# Sheet2.net
KiCad netlist of a schematic drawn in Altium Designer
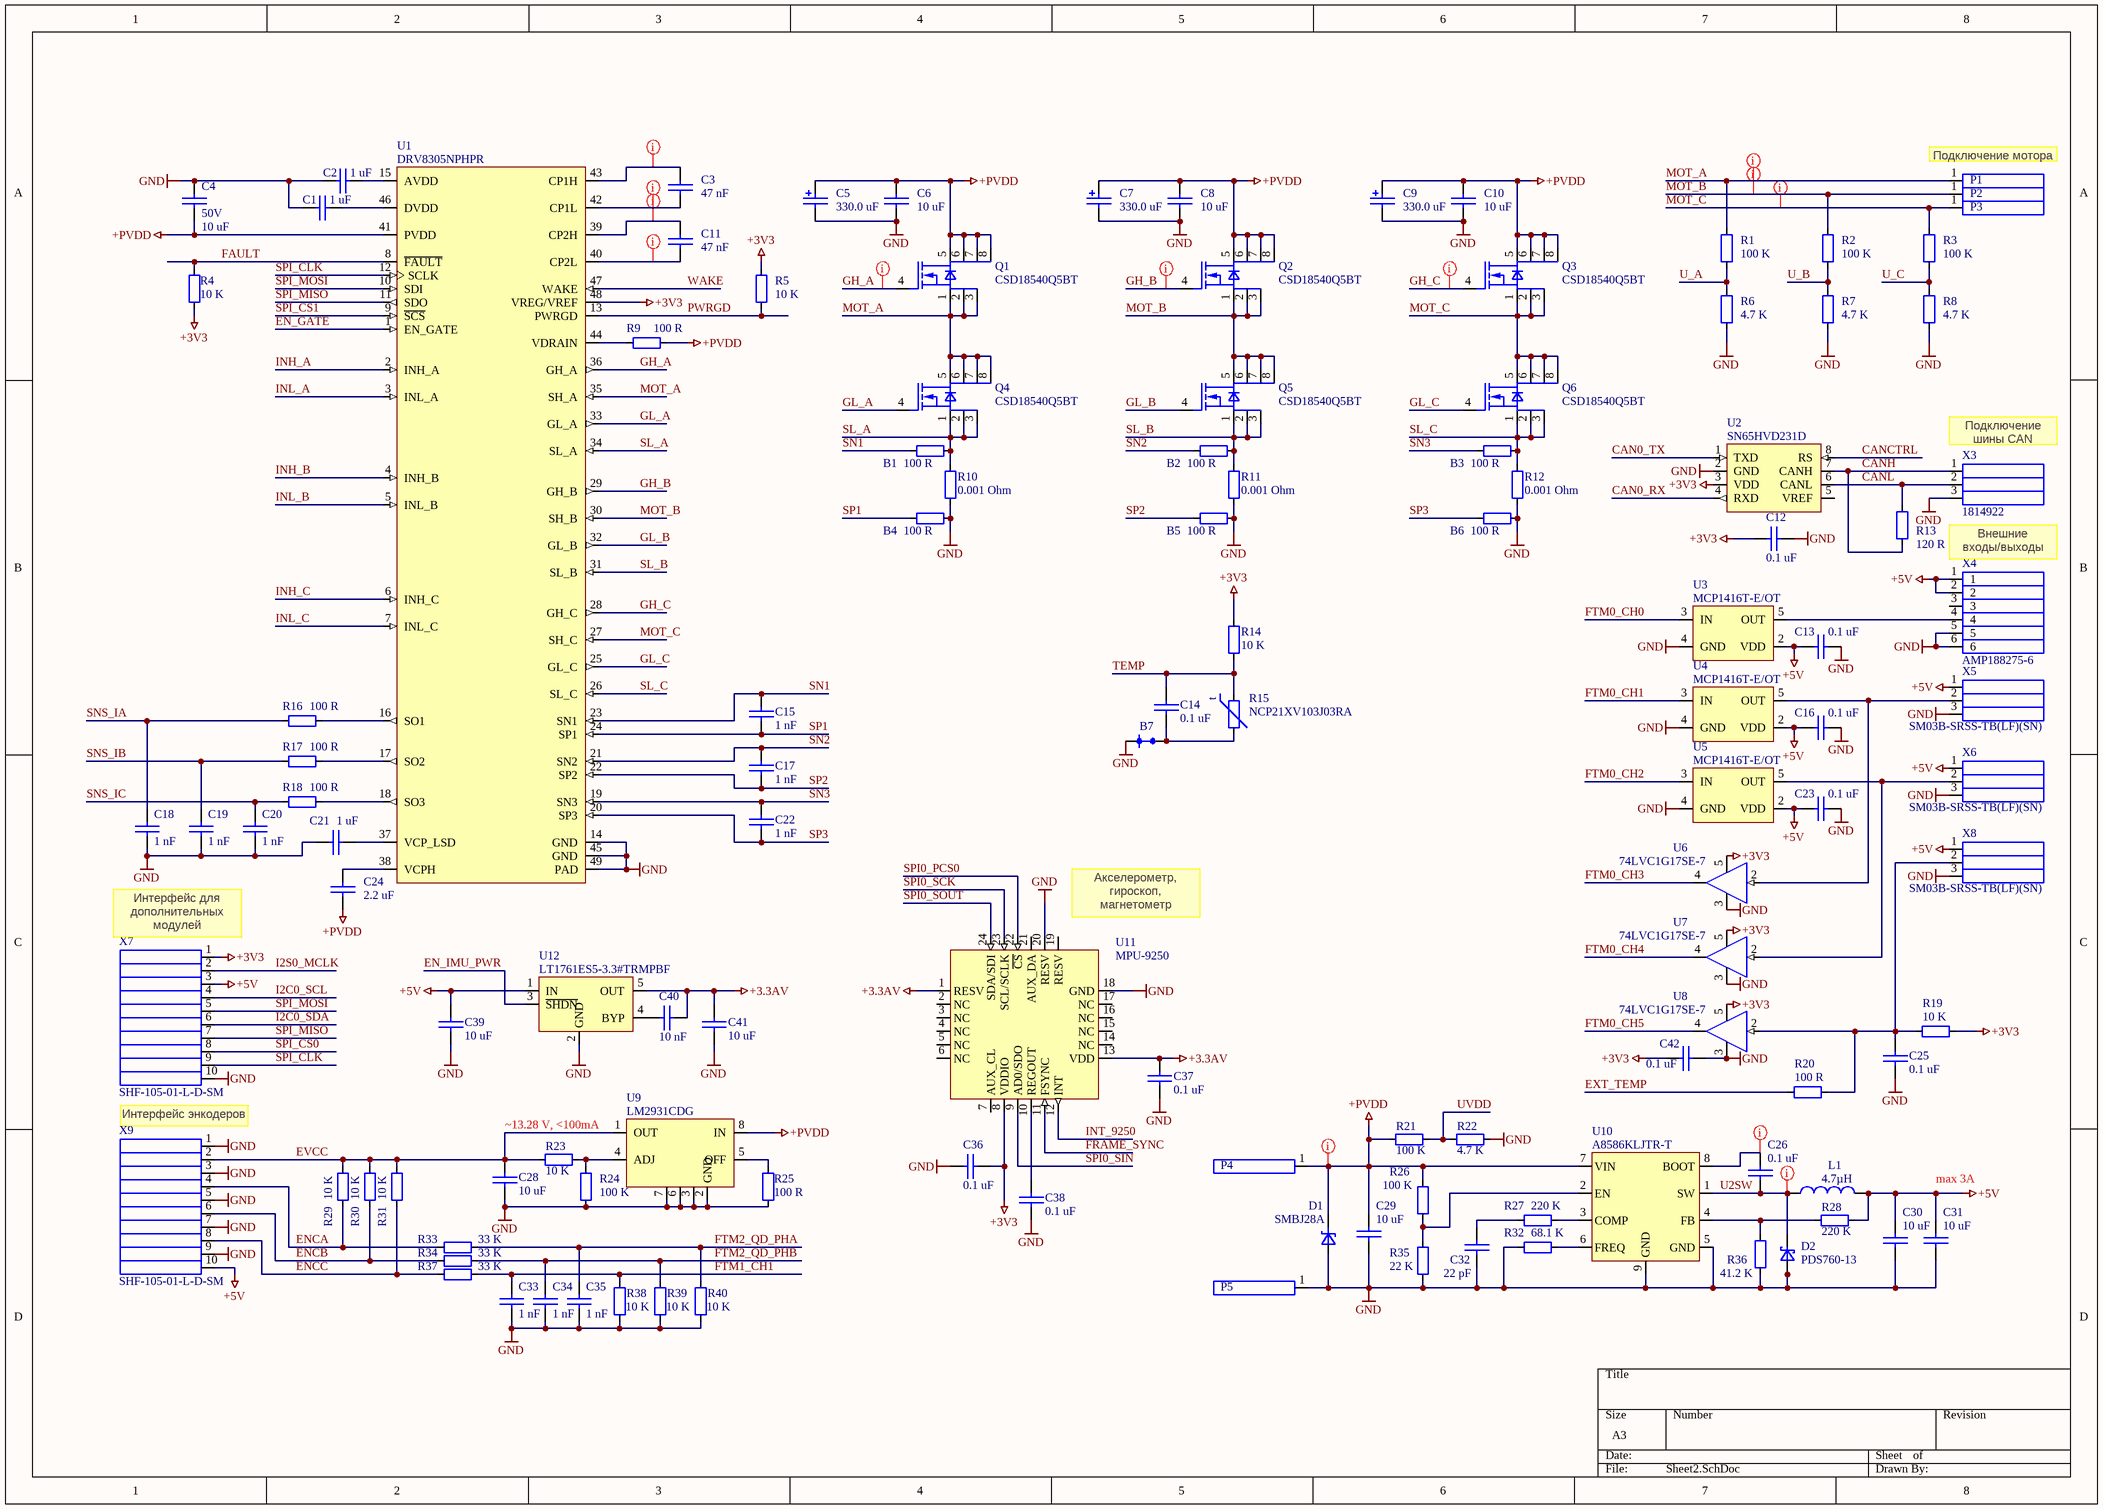
[diagram p0: Sheet2.SchDoc]

(export (version "E")
  (design (tool "Eeschema 10.0.6"))
  (components
    (comp (ref "B1")
      (value "100 R")
      (footprint "0603")
      (description "100 R, 1%, 0603, SMD Resistor, Taped")
      (fields (field (name "MANUFACTURER") "Vishay") (field (name "TOLERANCE") "±1%"))
      (libsource (lib "ea_Resistors") (part "RL0603E100-1"))
    )
    (comp (ref "B2")
      (value "100 R")
      (footprint "0603")
      (description "100 R, 1%, 0603, SMD Resistor, Taped")
      (fields (field (name "MANUFACTURER") "Vishay") (field (name "TOLERANCE") "±1%"))
      (libsource (lib "ea_Resistors") (part "RL0603E100-1"))
    )
    (comp (ref "B3")
      (value "100 R")
      (footprint "0603")
      (description "100 R, 1%, 0603, SMD Resistor, Taped")
      (fields (field (name "MANUFACTURER") "Vishay") (field (name "TOLERANCE") "±1%"))
      (libsource (lib "ea_Resistors") (part "RL0603E100-1"))
    )
    (comp (ref "B4")
      (value "100 R")
      (footprint "0603")
      (description "100 R, 1%, 0603, SMD Resistor, Taped")
      (fields (field (name "MANUFACTURER") "Vishay") (field (name "TOLERANCE") "±1%"))
      (libsource (lib "ea_Resistors") (part "RL0603E100-1"))
    )
    (comp (ref "B5")
      (value "100 R")
      (footprint "0603")
      (description "100 R, 1%, 0603, SMD Resistor, Taped")
      (fields (field (name "MANUFACTURER") "Vishay") (field (name "TOLERANCE") "±1%"))
      (libsource (lib "ea_Resistors") (part "RL0603E100-1"))
    )
    (comp (ref "B6")
      (value "100 R")
      (footprint "0603")
      (description "100 R, 1%, 0603, SMD Resistor, Taped")
      (fields (field (name "MANUFACTURER") "Vishay") (field (name "TOLERANCE") "±1%"))
      (libsource (lib "ea_Resistors") (part "RL0603E100-1"))
    )
    (comp (ref "B7")
      (value "Net tie 0603")
      (footprint "Net tee 0603")
      (libsource (lib "ea_Mechanical") (part "Net tie 0603"))
    )
    (comp (ref "C1")
      (value "1 uF")
      (footprint "1608[0603]")
      (description "1 uF, 16V, 10%, X7R, 0603 SMD MLC Capacitor, -55°C ~ 125°C")
      (fields (field (name "TOLERANCE") "±10%") (field (name "MANUFACTURER") "TDK Corporation"))
      (libsource (lib "ea_Capacitors") (part "C1608X7R1C105K080AC"))
    )
    (comp (ref "C2")
      (value "1 uF")
      (footprint "1608[0603]")
      (description "1 uF, 16V, 10%, X7R, 0603 SMD MLC Capacitor, -55°C ~ 125°C")
      (fields (field (name "TOLERANCE") "±10%") (field (name "MANUFACTURER") "TDK Corporation"))
      (libsource (lib "ea_Capacitors") (part "C1608X7R1C105K080AC"))
    )
    (comp (ref "C3")
      (value "47 nF")
      (footprint "1608[0603]")
      (description "47 nF, 100V, 10%, X7R, 0603 SMD MLC Capacitor, -55°C ~ 125°C")
      (fields (field (name "TOLERANCE") "±10%") (field (name "MANUFACTURER") "Kemet"))
      (libsource (lib "ea_Capacitors") (part "C0603C473K1RACTU"))
    )
    (comp (ref "C4")
      (value "10 uF")
      (footprint "3225[1210]")
      (description "10uF, 50V, 20%, Y5V (F), 1210")
      (fields
        (field (name "MANUFACTURER") "Murata Electronics North America")
        (field (name "TOLERANCE") "20%")
        (field (name "VOLTAGE") "50V")
      )
      (libsource (lib "ea_Capacitors") (part "GRM32DF51H106ZA01L"))
    )
    (comp (ref "C5")
      (value "330.0 uF")
      (footprint "UUD1V331MNL1GS")
      (description "330 uF, 50V, 120 mOhm @ 100kHz, 585 mA, 10x10, -50...+105 C")
      (fields (field (name "MANUFACTURER") "Panasonic Electronic Components") (field (name "VOLTAGE") "50 V"))
      (libsource (lib "ea_Capacitors") (part "EEE-FT1H331AP"))
    )
    (comp (ref "C6")
      (value "10 uF")
      (footprint "3225[1210]")
      (description "10uF, 50V, 20%, Y5V (F), 1210")
      (fields
        (field (name "MANUFACTURER") "Murata Electronics North America")
        (field (name "TOLERANCE") "20%")
      )
      (libsource (lib "ea_Capacitors") (part "GRM32DF51H106ZA01L"))
    )
    (comp (ref "C7")
      (value "330.0 uF")
      (footprint "UUD1V331MNL1GS")
      (description "330 uF, 50V, 120 mOhm @ 100kHz, 585 mA, 10x10, -50...+105 C")
      (fields (field (name "MANUFACTURER") "Panasonic Electronic Components") (field (name "VOLTAGE") "50 V"))
      (libsource (lib "ea_Capacitors") (part "EEE-FT1H331AP"))
    )
    (comp (ref "C8")
      (value "10 uF")
      (footprint "3225[1210]")
      (description "10uF, 50V, 20%, Y5V (F), 1210")
      (fields
        (field (name "MANUFACTURER") "Murata Electronics North America")
        (field (name "TOLERANCE") "20%")
      )
      (libsource (lib "ea_Capacitors") (part "GRM32DF51H106ZA01L"))
    )
    (comp (ref "C9")
      (value "330.0 uF")
      (footprint "UUD1V331MNL1GS")
      (description "330 uF, 50V, 120 mOhm @ 100kHz, 585 mA, 10x10, -50...+105 C")
      (fields (field (name "MANUFACTURER") "Panasonic Electronic Components") (field (name "VOLTAGE") "50 V"))
      (libsource (lib "ea_Capacitors") (part "EEE-FT1H331AP"))
    )
    (comp (ref "C10")
      (value "10 uF")
      (footprint "3225[1210]")
      (description "10uF, 50V, 20%, Y5V (F), 1210")
      (fields
        (field (name "MANUFACTURER") "Murata Electronics North America")
        (field (name "TOLERANCE") "20%")
      )
      (libsource (lib "ea_Capacitors") (part "GRM32DF51H106ZA01L"))
    )
    (comp (ref "C11")
      (value "47 nF")
      (footprint "1608[0603]")
      (description "47 nF, 100V, 10%, X7R, 0603 SMD MLC Capacitor, -55°C ~ 125°C")
      (fields (field (name "TOLERANCE") "±10%") (field (name "MANUFACTURER") "Kemet"))
      (libsource (lib "ea_Capacitors") (part "C0603C473K1RACTU"))
    )
    (comp (ref "C12")
      (value "0.1 uF")
      (footprint "1608[0603]")
      (description "0.1 uF, 50V, 10% , X7R,  0603 SMD MLC Capacitor")
      (fields (field (name "TOLERANCE") "±10%") (field (name "MANUFACTURER") "WALSIN"))
      (libsource (lib "ea_Capacitors") (part "CVNF100K0603-25"))
    )
    (comp (ref "C13")
      (value "0.1 uF")
      (footprint "1608[0603]")
      (description "0.1 uF, 50V, 10% , X7R,  0603 SMD MLC Capacitor")
      (fields (field (name "TOLERANCE") "±10%") (field (name "MANUFACTURER") "WALSIN"))
      (libsource (lib "ea_Capacitors") (part "CVNF100K0603-25"))
    )
    (comp (ref "C14")
      (value "0.1 uF")
      (footprint "1608[0603]")
      (description "0.1 uF, 50V, 10% , X7R,  0603 SMD MLC Capacitor")
      (fields (field (name "TOLERANCE") "±10%") (field (name "MANUFACTURER") "WALSIN"))
      (libsource (lib "ea_Capacitors") (part "CVNF100K0603-25"))
    )
    (comp (ref "C15")
      (value "1 nF")
      (footprint "1608[0603]")
      (description "1 nF, 50V, 10%, X7R, 0603 SMD MLC Capacitor")
      (fields (field (name "TOLERANCE") "±10%") (field (name "MANUFACTURER") "Darfon"))
      (libsource (lib "ea_Capacitors") (part "CVNF1.0K0603"))
    )
    (comp (ref "C16")
      (value "0.1 uF")
      (footprint "1608[0603]")
      (description "0.1 uF, 50V, 10% , X7R,  0603 SMD MLC Capacitor")
      (fields (field (name "TOLERANCE") "±10%") (field (name "MANUFACTURER") "WALSIN"))
      (libsource (lib "ea_Capacitors") (part "CVNF100K0603-25"))
    )
    (comp (ref "C17")
      (value "1 nF")
      (footprint "1608[0603]")
      (description "1 nF, 50V, 10%, X7R, 0603 SMD MLC Capacitor")
      (fields (field (name "TOLERANCE") "±10%") (field (name "MANUFACTURER") "Darfon"))
      (libsource (lib "ea_Capacitors") (part "CVNF1.0K0603"))
    )
    (comp (ref "C18")
      (value "1 nF")
      (footprint "1608[0603]")
      (description "1 nF, 50V, 10%, X7R, 0603 SMD MLC Capacitor")
      (fields (field (name "TOLERANCE") "±10%") (field (name "MANUFACTURER") "Darfon"))
      (libsource (lib "ea_Capacitors") (part "CVNF1.0K0603"))
    )
    (comp (ref "C19")
      (value "1 nF")
      (footprint "1608[0603]")
      (description "1 nF, 50V, 10%, X7R, 0603 SMD MLC Capacitor")
      (fields (field (name "TOLERANCE") "±10%") (field (name "MANUFACTURER") "Darfon"))
      (libsource (lib "ea_Capacitors") (part "CVNF1.0K0603"))
    )
    (comp (ref "C20")
      (value "1 nF")
      (footprint "1608[0603]")
      (description "1 nF, 50V, 10%, X7R, 0603 SMD MLC Capacitor")
      (fields (field (name "TOLERANCE") "±10%") (field (name "MANUFACTURER") "Darfon"))
      (libsource (lib "ea_Capacitors") (part "CVNF1.0K0603"))
    )
    (comp (ref "C21")
      (value "1 uF")
      (footprint "1608[0603]")
      (description "1 uF, 16V, 10%, X7R, 0603 SMD MLC Capacitor, -55°C ~ 125°C")
      (fields (field (name "TOLERANCE") "±10%") (field (name "MANUFACTURER") "TDK Corporation"))
      (libsource (lib "ea_Capacitors") (part "C1608X7R1C105K080AC"))
    )
    (comp (ref "C22")
      (value "1 nF")
      (footprint "1608[0603]")
      (description "1 nF, 50V, 10%, X7R, 0603 SMD MLC Capacitor")
      (fields (field (name "TOLERANCE") "±10%") (field (name "MANUFACTURER") "Darfon"))
      (libsource (lib "ea_Capacitors") (part "CVNF1.0K0603"))
    )
    (comp (ref "C23")
      (value "0.1 uF")
      (footprint "1608[0603]")
      (description "0.1 uF, 50V, 10% , X7R,  0603 SMD MLC Capacitor")
      (fields (field (name "TOLERANCE") "±10%") (field (name "MANUFACTURER") "WALSIN"))
      (libsource (lib "ea_Capacitors") (part "CVNF100K0603-25"))
    )
    (comp (ref "C24")
      (value "2.2 uF")
      (footprint "3225[1210]")
      (description "2.2 uF, 100 V, ±10%, X7R, 1210, -55°C ~ 125°C")
      (fields
        (field (name "MANUFACTURER") "Murata Electronics North America")
        (field (name "TOLERANCE") "±10%")
      )
      (libsource (lib "ea_Capacitors") (part "GRM32ER72A225KA35L"))
    )
    (comp (ref "C25")
      (value "0.1 uF")
      (footprint "1608[0603]")
      (description "0.1 uF, 50V, 10% , X7R,  0603 SMD MLC Capacitor")
      (fields (field (name "TOLERANCE") "±10%") (field (name "MANUFACTURER") "WALSIN"))
      (libsource (lib "ea_Capacitors") (part "CVNF100K0603-25"))
    )
    (comp (ref "C26")
      (value "0.1 uF")
      (footprint "1608[0603]")
      (description "0.1 uF, 50V, 10% , X7R,  0603 SMD MLC Capacitor")
      (fields (field (name "TOLERANCE") "±10%") (field (name "MANUFACTURER") "WALSIN"))
      (libsource (lib "ea_Capacitors") (part "CVNF100K0603-25"))
    )
    (comp (ref "C28")
      (value "10 uF")
      (footprint "3225[1210]")
      (description "10uF, 50V, 20%, Y5V (F), 1210")
      (fields
        (field (name "MANUFACTURER") "Murata Electronics North America")
        (field (name "TOLERANCE") "20%")
      )
      (libsource (lib "ea_Capacitors") (part "GRM32DF51H106ZA01L"))
    )
    (comp (ref "C29")
      (value "10 uF")
      (footprint "3225[1210]")
      (description "10uF, 50V, 20%, Y5V (F), 1210")
      (fields
        (field (name "MANUFACTURER") "Murata Electronics North America")
        (field (name "TOLERANCE") "20%")
      )
      (libsource (lib "ea_Capacitors") (part "GRM32DF51H106ZA01L"))
    )
    (comp (ref "C30")
      (value "10 uF")
      (footprint "0805-1206")
      (description "CAP CER 10UF 10V 10% X5R 0805")
      (fields (field (name "MANUFACTURER") "Taiyo Yuden") (field (name "TOLERANCE") "10%"))
      (libsource (lib "ea_Capacitors") (part "LMK212F106ZG-T"))
    )
    (comp (ref "C31")
      (value "10 uF")
      (footprint "0805-1206")
      (description "CAP CER 10UF 10V 10% X5R 0805")
      (fields (field (name "MANUFACTURER") "Taiyo Yuden") (field (name "TOLERANCE") "10%"))
      (libsource (lib "ea_Capacitors") (part "LMK212F106ZG-T"))
    )
    (comp (ref "C32")
      (value "22 pF")
      (footprint "1608[0603]")
      (description "22 pF, 50V, 5%, NP0, 0603 SMD MLC Capacitor")
      (fields (field (name "MANUFACTURER") "Darfon") (field (name "TOLERANCE") "5%"))
      (libsource (lib "ea_Capacitors") (part "CCPF022K0603"))
    )
    (comp (ref "C33")
      (value "1 nF")
      (footprint "1608[0603]")
      (description "1 nF, 50V, 10%, X7R, 0603 SMD MLC Capacitor")
      (fields (field (name "TOLERANCE") "±10%") (field (name "MANUFACTURER") "Darfon"))
      (libsource (lib "ea_Capacitors") (part "CVNF1.0K0603"))
    )
    (comp (ref "C34")
      (value "1 nF")
      (footprint "1608[0603]")
      (description "1 nF, 50V, 10%, X7R, 0603 SMD MLC Capacitor")
      (fields (field (name "TOLERANCE") "±10%") (field (name "MANUFACTURER") "Darfon"))
      (libsource (lib "ea_Capacitors") (part "CVNF1.0K0603"))
    )
    (comp (ref "C35")
      (value "1 nF")
      (footprint "1608[0603]")
      (description "1 nF, 50V, 10%, X7R, 0603 SMD MLC Capacitor")
      (fields (field (name "TOLERANCE") "±10%") (field (name "MANUFACTURER") "Darfon"))
      (libsource (lib "ea_Capacitors") (part "CVNF1.0K0603"))
    )
    (comp (ref "C36")
      (value "0.1 uF")
      (footprint "1608[0603]")
      (description "0.1 uF, 50V, 10% , X7R,  0603 SMD MLC Capacitor")
      (fields (field (name "MANUFACTURER") "WALSIN") (field (name "TOLERANCE") "±10%"))
      (libsource (lib "ea_Capacitors") (part "CVNF100K0603-25"))
    )
    (comp (ref "C37")
      (value "0.1 uF")
      (footprint "1608[0603]")
      (description "0.1 uF, 50V, 10% , X7R,  0603 SMD MLC Capacitor")
      (fields (field (name "MANUFACTURER") "WALSIN") (field (name "TOLERANCE") "±10%"))
      (libsource (lib "ea_Capacitors") (part "CVNF100K0603-25"))
    )
    (comp (ref "C38")
      (value "0.1 uF")
      (footprint "1608[0603]")
      (description "0.1 uF, 50V, 10% , X7R,  0603 SMD MLC Capacitor")
      (fields (field (name "MANUFACTURER") "WALSIN") (field (name "TOLERANCE") "±10%"))
      (libsource (lib "ea_Capacitors") (part "CVNF100K0603-25"))
    )
    (comp (ref "C39")
      (value "10 uF")
      (footprint "MK212-G (0805)")
      (description "10 uF, 10V, X7R, ±10%, 0805, -55°C ~ 125°C")
      (fields (field (name "MANUFACTURER") "Taiyo Yuden") (field (name "TOLERANCE") "±10%"))
      (libsource (lib "ea_Capacitors") (part "LMK212B7106KG-TD"))
    )
    (comp (ref "C40")
      (value "10 nF")
      (footprint "1608[0603]")
      (description "10 nF, 50V, 10%, X7R, 0603 SMD MLC Capacitor")
      (fields (field (name "TOLERANCE") "±10%") (field (name "MANUFACTURER") "Murata Electronics"))
      (libsource (lib "ea_Capacitors") (part "CVNF010K0603"))
    )
    (comp (ref "C41")
      (value "10 uF")
      (footprint "MK212-G (0805)")
      (description "10 uF, 10V, X7R, ±10%, 0805, -55°C ~ 125°C")
      (fields (field (name "MANUFACTURER") "Taiyo Yuden") (field (name "TOLERANCE") "±10%"))
      (libsource (lib "ea_Capacitors") (part "LMK212B7106KG-TD"))
    )
    (comp (ref "C42")
      (value "0.1 uF")
      (footprint "1608[0603]")
      (description "0.1 uF, 50V, 10% , X7R,  0603 SMD MLC Capacitor")
      (fields (field (name "TOLERANCE") "±10%") (field (name "MANUFACTURER") "WALSIN"))
      (libsource (lib "ea_Capacitors") (part "CVNF100K0603-25"))
    )
    (comp (ref "D1")
      (value "SMBJ28A")
      (footprint "DO-214AA_SMBJ")
      (description "DIODE TVS 28V 600W UNI 5% SMD")
      (fields (field (name "MANUFACTURER") "Littelfuse") (field (name "PARTNUM") "SMBJ28ABCT-ND"))
      (libsource (lib "ea_TVS_protection") (part "SMBJ28A"))
    )
    (comp (ref "D2")
      (value "PDS760-13")
      (footprint "PowerDI 5")
      (description "Schottky Power Rectifier 7A, 60V, SMA")
      (fields (field (name "MANUFACTURER") "VISHAY") (field (name "PARTNUM") "PDS760DICT-ND"))
      (libsource (lib "ea_Diodes") (part "PDS760-13"))
    )
    (comp (ref "L1")
      (value "4.7µH")
      (footprint "SRU8043 Bourns")
      (description "4.7µH, 4.6 A, 0.017Ohms, ±30%, -40°C ~ 125°C")
      (fields (field (name "MANUFACTURER") "Bourns Inc.") (field (name "PARTNUM") "SRU8043-4R7YCT-ND"))
      (libsource (lib "ea_Inductors") (part "SRU8043-4R7Y"))
    )
    (comp (ref "P1")
      (value "Keystone 1212")
      (footprint "Keystone 1212")
      (description "(4.75mm) Quick Connect Male Solder Connector Non-Insulated")
      (fields (field (name "MANUFACTURER") "Keystone Electronics") (field (name "PARTNUM") "36-1212-ND"))
      (libsource (lib "ea_Connectors_Power") (part "Keystone_1212"))
    )
    (comp (ref "P2")
      (value "Keystone 1212")
      (footprint "Keystone 1212")
      (description "(4.75mm) Quick Connect Male Solder Connector Non-Insulated")
      (fields (field (name "MANUFACTURER") "Keystone Electronics") (field (name "PARTNUM") "36-1212-ND"))
      (libsource (lib "ea_Connectors_Power") (part "Keystone_1212"))
    )
    (comp (ref "P3")
      (value "Keystone 1212")
      (footprint "Keystone 1212")
      (description "(4.75mm) Quick Connect Male Solder Connector Non-Insulated")
      (fields (field (name "MANUFACTURER") "Keystone Electronics") (field (name "PARTNUM") "36-1212-ND"))
      (libsource (lib "ea_Connectors_Power") (part "Keystone_1212"))
    )
    (comp (ref "P4")
      (value "Keystone 1212")
      (footprint "Keystone 1212")
      (description "(4.75mm) Quick Connect Male Solder Connector Non-Insulated")
      (fields (field (name "MANUFACTURER") "Keystone Electronics") (field (name "PARTNUM") "36-1212-ND"))
      (libsource (lib "ea_Connectors_Power") (part "Keystone_1212"))
    )
    (comp (ref "P5")
      (value "Keystone 1212")
      (footprint "Keystone 1212")
      (description "(4.75mm) Quick Connect Male Solder Connector Non-Insulated")
      (fields (field (name "MANUFACTURER") "Keystone Electronics") (field (name "PARTNUM") "36-1212-ND"))
      (libsource (lib "ea_Connectors_Power") (part "Keystone_1212"))
    )
    (comp (ref "Q1")
      (value "CSD18540Q5BT")
      (footprint "TI Q5B")
      (description "MOSFET N-CH, 100 A, 60V, 0.0022 Ohm")
      (fields (field (name "MANUFACTURER") "Texas Instruments") (field (name "PARTNUM") "296-37963-1-ND"))
      (libsource (lib "ea_MOSFET_&_drivers") (part "CSD18540Q5BT"))
    )
    (comp (ref "Q2")
      (value "CSD18540Q5BT")
      (footprint "TI Q5B")
      (description "MOSFET N-CH, 100 A, 60V, 0.0022 Ohm")
      (fields (field (name "MANUFACTURER") "Texas Instruments") (field (name "PARTNUM") "296-37963-1-ND"))
      (libsource (lib "ea_MOSFET_&_drivers") (part "CSD18540Q5BT"))
    )
    (comp (ref "Q3")
      (value "CSD18540Q5BT")
      (footprint "TI Q5B")
      (description "MOSFET N-CH, 100 A, 60V, 0.0022 Ohm")
      (fields (field (name "MANUFACTURER") "Texas Instruments") (field (name "PARTNUM") "296-37963-1-ND"))
      (libsource (lib "ea_MOSFET_&_drivers") (part "CSD18540Q5BT"))
    )
    (comp (ref "Q4")
      (value "CSD18540Q5BT")
      (footprint "TI Q5B")
      (description "MOSFET N-CH, 100 A, 60V, 0.0022 Ohm")
      (fields (field (name "MANUFACTURER") "Texas Instruments") (field (name "PARTNUM") "296-37963-1-ND"))
      (libsource (lib "ea_MOSFET_&_drivers") (part "CSD18540Q5BT"))
    )
    (comp (ref "Q5")
      (value "CSD18540Q5BT")
      (footprint "TI Q5B")
      (description "MOSFET N-CH, 100 A, 60V, 0.0022 Ohm")
      (fields (field (name "MANUFACTURER") "Texas Instruments") (field (name "PARTNUM") "296-37963-1-ND"))
      (libsource (lib "ea_MOSFET_&_drivers") (part "CSD18540Q5BT"))
    )
    (comp (ref "Q6")
      (value "CSD18540Q5BT")
      (footprint "TI Q5B")
      (description "MOSFET N-CH, 100 A, 60V, 0.0022 Ohm")
      (fields (field (name "MANUFACTURER") "Texas Instruments") (field (name "PARTNUM") "296-37963-1-ND"))
      (libsource (lib "ea_MOSFET_&_drivers") (part "CSD18540Q5BT"))
    )
    (comp (ref "R1")
      (value "100 K")
      (footprint "3216[1206]")
      (description "100 K, 1%, 1206, SMD Resistor, Taped")
      (fields (field (name "MANUFACTURER") "Yageo") (field (name "TOLERANCE") "±1%"))
      (libsource (lib "ea_Resistors") (part "CRCW1206100KFKEA"))
    )
    (comp (ref "R2")
      (value "100 K")
      (footprint "3216[1206]")
      (description "100 K, 1%, 1206, SMD Resistor, Taped")
      (fields (field (name "MANUFACTURER") "Yageo") (field (name "TOLERANCE") "±1%"))
      (libsource (lib "ea_Resistors") (part "CRCW1206100KFKEA"))
    )
    (comp (ref "R3")
      (value "100 K")
      (footprint "3216[1206]")
      (description "100 K, 1%, 1206, SMD Resistor, Taped")
      (fields (field (name "MANUFACTURER") "Yageo") (field (name "TOLERANCE") "±1%"))
      (libsource (lib "ea_Resistors") (part "CRCW1206100KFKEA"))
    )
    (comp (ref "R4")
      (value "10 K")
      (footprint "0603")
      (description "10 K, 1%, 0603, SMD Resistor, Taped")
      (fields (field (name "MANUFACTURER") "Vishay Dale") (field (name "TOLERANCE") "±1%"))
      (libsource (lib "ea_Resistors") (part "RL0603K010-1"))
    )
    (comp (ref "R5")
      (value "10 K")
      (footprint "0603")
      (description "10 K, 1%, 0603, SMD Resistor, Taped")
      (fields (field (name "MANUFACTURER") "Vishay Dale") (field (name "TOLERANCE") "±1%"))
      (libsource (lib "") (part "RL0603K010-1_1"))
    )
    (comp (ref "R6")
      (value "4.7 K")
      (footprint "0603")
      (description "4.7 K, 1%, 0603, SMD Resistor, Taped")
      (fields (field (name "MANUFACTURER") "Vishay") (field (name "TOLERANCE") "±1%"))
      (libsource (lib "ea_Resistors") (part "RL0603K004.7-1"))
    )
    (comp (ref "R7")
      (value "4.7 K")
      (footprint "0603")
      (description "4.7 K, 1%, 0603, SMD Resistor, Taped")
      (fields (field (name "MANUFACTURER") "Vishay") (field (name "TOLERANCE") "±1%"))
      (libsource (lib "ea_Resistors") (part "RL0603K004.7-1"))
    )
    (comp (ref "R8")
      (value "4.7 K")
      (footprint "0603")
      (description "4.7 K, 1%, 0603, SMD Resistor, Taped")
      (fields (field (name "MANUFACTURER") "Vishay") (field (name "TOLERANCE") "±1%"))
      (libsource (lib "ea_Resistors") (part "RL0603K004.7-1"))
    )
    (comp (ref "R9")
      (value "100 R")
      (footprint "0603")
      (description "100 R, 1%, 0603, SMD Resistor, Taped")
      (fields (field (name "MANUFACTURER") "Vishay") (field (name "TOLERANCE") "±1%"))
      (libsource (lib "ea_Resistors") (part "RL0603E100-1"))
    )
    (comp (ref "R10")
      (value "0.001 Ohm")
      (footprint "CSNL2512 1mOhm")
      (description "Curr.sens.res. 0.001 OHM, 2W, 1% , 63A max, ±50ppm/°C, 2512 (6432 Metric)")
      (fields (field (name "MANUFACTURER") "Stackpole Electronics Inc.") (field (name "TOLERANCE") "±1%"))
      (libsource (lib "ea_Resistors") (part "CSNL2512FT1L00"))
    )
    (comp (ref "R11")
      (value "0.001 Ohm")
      (footprint "CSNL2512 1mOhm")
      (description "Curr.sens.res. 0.001 OHM, 2W, 1% , 63A max, ±50ppm/°C, 2512 (6432 Metric)")
      (fields (field (name "MANUFACTURER") "Stackpole Electronics Inc.") (field (name "TOLERANCE") "±1%"))
      (libsource (lib "ea_Resistors") (part "CSNL2512FT1L00"))
    )
    (comp (ref "R12")
      (value "0.001 Ohm")
      (footprint "CSNL2512 1mOhm")
      (description "Curr.sens.res. 0.001 OHM, 2W, 1% , 63A max, ±50ppm/°C, 2512 (6432 Metric)")
      (fields (field (name "MANUFACTURER") "Stackpole Electronics Inc.") (field (name "TOLERANCE") "±1%"))
      (libsource (lib "ea_Resistors") (part "CSNL2512FT1L00"))
    )
    (comp (ref "R13")
      (value "120 R")
      (footprint "0603")
      (description "120 R, 1%, 0603, SMD Resistor, Taped")
      (fields (field (name "MANUFACTURER") "Vishay") (field (name "TOLERANCE") "±1%"))
      (libsource (lib "ea_Resistors") (part "RL0603E120-1"))
    )
    (comp (ref "R14")
      (value "10 K")
      (footprint "0603")
      (description "10 K, 1%, 0603, SMD Resistor, Taped")
      (fields (field (name "MANUFACTURER") "Vishay Dale") (field (name "TOLERANCE") "±1%"))
      (libsource (lib "") (part "RL0603K010-1_1"))
    )
    (comp (ref "R15")
      (value "NCP21XV103J03RA")
      (footprint "0805")
      (description "Thermistor 10k, 0805, NTC")
      (fields (field (name "MANUFACTURER") "Murata") (field (name "PARTNUM") "490-2456-1-ND"))
      (libsource (lib "ea_IC_sensors") (part "NCP21XV103J03RA"))
    )
    (comp (ref "R16")
      (value "100 R")
      (footprint "0603")
      (description "100 R, 1%, 0603, SMD Resistor, Taped")
      (fields (field (name "MANUFACTURER") "Vishay") (field (name "TOLERANCE") "±1%"))
      (libsource (lib "ea_Resistors") (part "RL0603E100-1"))
    )
    (comp (ref "R17")
      (value "100 R")
      (footprint "0603")
      (description "100 R, 1%, 0603, SMD Resistor, Taped")
      (fields (field (name "MANUFACTURER") "Vishay") (field (name "TOLERANCE") "±1%"))
      (libsource (lib "ea_Resistors") (part "RL0603E100-1"))
    )
    (comp (ref "R18")
      (value "100 R")
      (footprint "0603")
      (description "100 R, 1%, 0603, SMD Resistor, Taped")
      (fields (field (name "MANUFACTURER") "Vishay") (field (name "TOLERANCE") "±1%"))
      (libsource (lib "ea_Resistors") (part "RL0603E100-1"))
    )
    (comp (ref "R19")
      (value "10 K")
      (footprint "0603")
      (description "10 K, 1%, 0603, SMD Resistor, Taped")
      (fields (field (name "MANUFACTURER") "Vishay Dale") (field (name "TOLERANCE") "±1%"))
      (libsource (lib "") (part "RL0603K010-1_2"))
    )
    (comp (ref "R20")
      (value "100 R")
      (footprint "0603")
      (description "100 R, 1%, 0603, SMD Resistor, Taped")
      (fields (field (name "MANUFACTURER") "Vishay") (field (name "TOLERANCE") "±1%"))
      (libsource (lib "ea_Resistors") (part "RL0603E100-1"))
    )
    (comp (ref "R21")
      (value "100 K")
      (footprint "0603")
      (description "100 K, 1%, 0603, SMD Resistor, Taped")
      (fields (field (name "MANUFACTURER") "Vishay") (field (name "TOLERANCE") "±1%"))
      (libsource (lib "") (part "RL0603K100-1_2"))
    )
    (comp (ref "R22")
      (value "4.7 K")
      (footprint "0603")
      (description "4.7 K, 1%, 0603, SMD Resistor, Taped")
      (fields (field (name "MANUFACTURER") "Vishay") (field (name "TOLERANCE") "±1%"))
      (libsource (lib "ea_Resistors") (part "RL0603K004.7-1"))
    )
    (comp (ref "R23")
      (value "10 K")
      (footprint "0603")
      (description "10 K, 1%, 0603, SMD Resistor, Taped")
      (fields (field (name "MANUFACTURER") "Vishay Dale") (field (name "TOLERANCE") "±1%"))
      (libsource (lib "") (part "RL0603K010-1_2"))
    )
    (comp (ref "R24")
      (value "100 K")
      (footprint "0603")
      (description "100 K, 1%, 0603, SMD Resistor, Taped")
      (fields (field (name "MANUFACTURER") "Vishay") (field (name "TOLERANCE") "±1%"))
      (libsource (lib "") (part "RL0603K100-1_1"))
    )
    (comp (ref "R25")
      (value "100 R")
      (footprint "0603")
      (description "100 R, 1%, 0603, SMD Resistor, Taped")
      (fields (field (name "MANUFACTURER") "Vishay") (field (name "TOLERANCE") "±1%"))
      (libsource (lib "") (part "RL0603E100-1_1"))
    )
    (comp (ref "R26")
      (value "100 K")
      (footprint "0603")
      (description "100 K, 1%, 0603, SMD Resistor, Taped")
      (fields (field (name "MANUFACTURER") "Vishay") (field (name "TOLERANCE") "±1%"))
      (libsource (lib "ea_Resistors") (part "RL0603K100-1"))
    )
    (comp (ref "R27")
      (value "220 K")
      (footprint "0603")
      (description "220 K, 1%, 0603, SMD Resistor, Taped")
      (fields (field (name "MANUFACTURER") "Yageo") (field (name "TOLERANCE") "±1%"))
      (libsource (lib "ea_Resistors") (part "RL0603K220-1"))
    )
    (comp (ref "R28")
      (value "220 K")
      (footprint "0603")
      (description "220 K, 1%, 0603, SMD Resistor, Taped")
      (fields (field (name "MANUFACTURER") "Yageo") (field (name "TOLERANCE") "±1%"))
      (libsource (lib "ea_Resistors") (part "RL0603K220-1"))
    )
    (comp (ref "R29")
      (value "10 K")
      (footprint "0603")
      (description "10 K, 1%, 0603, SMD Resistor, Taped")
      (fields (field (name "MANUFACTURER") "Vishay Dale") (field (name "TOLERANCE") "±1%"))
      (libsource (lib "") (part "RL0603K010-1_1"))
    )
    (comp (ref "R30")
      (value "10 K")
      (footprint "0603")
      (description "10 K, 1%, 0603, SMD Resistor, Taped")
      (fields (field (name "MANUFACTURER") "Vishay Dale") (field (name "TOLERANCE") "±1%"))
      (libsource (lib "") (part "RL0603K010-1_1"))
    )
    (comp (ref "R31")
      (value "10 K")
      (footprint "0603")
      (description "10 K, 1%, 0603, SMD Resistor, Taped")
      (fields (field (name "MANUFACTURER") "Vishay Dale") (field (name "TOLERANCE") "±1%"))
      (libsource (lib "") (part "RL0603K010-1_1"))
    )
    (comp (ref "R32")
      (value "68.1 K")
      (footprint "0603")
      (description "68.1 K, 1%, 0603, SMD Resistor, -55°C ~ 155°C")
      (fields (field (name "MANUFACTURER") "Yageo") (field (name "TOLERANCE") "±1%"))
      (libsource (lib "ea_Resistors") (part "RC0603FR-0768K1L"))
    )
    (comp (ref "R33")
      (value "33 K")
      (footprint "0603")
      (description "33 K, 1%, 0603, SMD Resistor, Taped")
      (fields (field (name "MANUFACTURER") "YAGEO AMERICA CORPORATION") (field (name "TOLERANCE") "±1%"))
      (libsource (lib "ea_Resistors") (part "RL0603K033-1_1"))
    )
    (comp (ref "R34")
      (value "33 K")
      (footprint "0603")
      (description "33 K, 1%, 0603, SMD Resistor, Taped")
      (fields (field (name "MANUFACTURER") "YAGEO AMERICA CORPORATION") (field (name "TOLERANCE") "±1%"))
      (libsource (lib "ea_Resistors") (part "RL0603K033-1_1"))
    )
    (comp (ref "R35")
      (value "22 K")
      (footprint "0603")
      (description "22 K, 1%, 0603, SMD Resistor, Taped")
      (fields (field (name "MANUFACTURER") "Vishay") (field (name "TOLERANCE") "±1%"))
      (libsource (lib "ea_Resistors") (part "RL0603K022-1"))
    )
    (comp (ref "R36")
      (value "41.2 K")
      (footprint "0603")
      (description "41.2 K, 1%, 0603, SMD Resistor, -55°C ~ 155°C")
      (fields (field (name "MANUFACTURER") "Yageo") (field (name "TOLERANCE") "±1%"))
      (libsource (lib "ea_Resistors") (part "RC0603FR-0741K2L"))
    )
    (comp (ref "R37")
      (value "33 K")
      (footprint "0603")
      (description "33 K, 1%, 0603, SMD Resistor, Taped")
      (fields (field (name "MANUFACTURER") "YAGEO AMERICA CORPORATION") (field (name "TOLERANCE") "±1%"))
      (libsource (lib "ea_Resistors") (part "RL0603K033-1_1"))
    )
    (comp (ref "R38")
      (value "10 K")
      (footprint "0603")
      (description "10 K, 1%, 0603, SMD Resistor, Taped")
      (fields (field (name "MANUFACTURER") "Vishay Dale") (field (name "TOLERANCE") "±1%"))
      (libsource (lib "ea_Resistors") (part "RL0603K010-1"))
    )
    (comp (ref "R39")
      (value "10 K")
      (footprint "0603")
      (description "10 K, 1%, 0603, SMD Resistor, Taped")
      (fields (field (name "MANUFACTURER") "Vishay Dale") (field (name "TOLERANCE") "±1%"))
      (libsource (lib "ea_Resistors") (part "RL0603K010-1"))
    )
    (comp (ref "R40")
      (value "10 K")
      (footprint "0603")
      (description "10 K, 1%, 0603, SMD Resistor, Taped")
      (fields (field (name "MANUFACTURER") "Vishay Dale") (field (name "TOLERANCE") "±1%"))
      (libsource (lib "ea_Resistors") (part "RL0603K010-1"))
    )
    (comp (ref "U1")
      (value "DRV8305NPHPR")
      (footprint "TI 48-HTQFP")
      (fields (field (name "MANUFACTURER") "Texas Instruments") (field (name "PARTNUM") "296-42659-1-ND"))
      (libsource (lib "ea_IC_motor_control") (part "DRV8305NPHPR"))
    )
    (comp (ref "U2")
      (value "SN65HVD231D")
      (footprint "SO-8")
      (description "3.3-V CAN TRANSCEIVERS SO-8")
      (fields (field (name "MANUFACTURER") "Texas Instruments") (field (name "PARTNUM") "296-12206-5-ND"))
      (libsource (lib "ea_IC_Interfaces") (part "SN65HVD231D"))
    )
    (comp (ref "U3")
      (value "MCP1416T-E/OT")
      (footprint "SOT23-5")
      (description "MOSFET drv 1.5A, 4.5-18 V,   -40..+150C, SOT-23-5")
      (fields
        (field (name "MANUFACTURER") "Microchip Technology")
        (field (name "PARTNUM") "MCP1416T-E/OTCT-ND")
      )
      (libsource (lib "ea_IC_drivers") (part "MCP1416T-E/OT"))
    )
    (comp (ref "U4")
      (value "MCP1416T-E/OT")
      (footprint "SOT23-5")
      (description "MOSFET drv 1.5A, 4.5-18 V,   -40..+150C, SOT-23-5")
      (fields
        (field (name "MANUFACTURER") "Microchip Technology")
        (field (name "PARTNUM") "MCP1416T-E/OTCT-ND")
      )
      (libsource (lib "ea_IC_drivers") (part "MCP1416T-E/OT"))
    )
    (comp (ref "U5")
      (value "MCP1416T-E/OT")
      (footprint "SOT23-5")
      (description "MOSFET drv 1.5A, 4.5-18 V,   -40..+150C, SOT-23-5")
      (fields
        (field (name "MANUFACTURER") "Microchip Technology")
        (field (name "PARTNUM") "MCP1416T-E/OTCT-ND")
      )
      (libsource (lib "ea_IC_drivers") (part "MCP1416T-E/OT"))
    )
    (comp (ref "U6")
      (value "74LVC1G17SE-7")
      (footprint "SOT-353 ON Semi")
      (description "IC SGL SCHMITT BUFFER SOT353")
      (fields
        (field (name "MANUFACTURER") "Diodes Incorporated")
        (field (name "PARTNUM") "74LVC1G17SE-7CT-ND")
      )
      (libsource (lib "ea_IC_Logic") (part "74LVC1G17SE-7"))
    )
    (comp (ref "U7")
      (value "74LVC1G17SE-7")
      (footprint "SOT-353 ON Semi")
      (description "IC SGL SCHMITT BUFFER SOT353")
      (fields
        (field (name "MANUFACTURER") "Diodes Incorporated")
        (field (name "PARTNUM") "74LVC1G17SE-7CT-ND")
      )
      (libsource (lib "ea_IC_Logic") (part "74LVC1G17SE-7"))
    )
    (comp (ref "U8")
      (value "74LVC1G17SE-7")
      (footprint "SOT-353 ON Semi")
      (description "IC SGL SCHMITT BUFFER SOT353")
      (fields
        (field (name "MANUFACTURER") "Diodes Incorporated")
        (field (name "PARTNUM") "74LVC1G17SE-7CT-ND")
      )
      (libsource (lib "ea_IC_Logic") (part "74LVC1G17SE-7"))
    )
    (comp (ref "U9")
      (value "LM2931CDG")
      (footprint "SO-8")
      (description "100 mA ,  Adj, SO-8")
      (fields (field (name "MANUFACTURER") "ON Semiconductor") (field (name "PARTNUM") "LM2931CDGOS-ND"))
      (libsource (lib "ea_IC_Power_Reg_Ref_Sw") (part "LM2931CDG"))
    )
    (comp (ref "U10")
      (value "A8586KLJTR-T")
      (footprint "LJ 8-Pin SOIC w termal pad")
      (description "IC REG 36V 3.5A, STEP DOWN 8-SOIC,-40°C ~ 150°C")
      (fields
        (field (name "MANUFACTURER") "Allegro Microsystems Inc")
        (field (name "PARTNUM") "620-1716-1-ND")
      )
      (libsource (lib "ea_IC_Power_Reg_Ref_Sw") (part "A8586KLJTR-T"))
    )
    (comp (ref "U11")
      (value "MPU-9250")
      (footprint "QFN-24 InvenSense")
      (description "Accelerometer, Gyroscope, Magnetometer, 3 Axis Sensor I2C, SPI Output, -40...+85 C, 24QFN")
      (fields (field (name "MANUFACTURER") "InvenSense") (field (name "PARTNUM") "1428-1019-1-ND"))
      (libsource (lib "ea_IC_sensors") (part "MPU-9250"))
    )
    (comp (ref "U12")
      (value "LT1761ES5-3.3#TRMPBF")
      (footprint "SOT23-5")
      (description "Low noice LDO 3.3V, Vin=2.7-20V, 300 mV at 100mA, -40...+125C, TSOT-23-5")
      (fields
        (field (name "MANUFACTURER") "Linear Technology")
        (field (name "PARTNUM") "LT1761ES5-3.3#TRMPBFCT-ND")
      )
      (libsource (lib "ea_IC_Power_Reg_Ref_Sw") (part "LT1761ES5-3.3#TRMPBF"))
    )
    (comp (ref "X3")
      (value "1814922")
      (footprint "1814922")
      (description "SSL Connector 3 Position Header, Male Pins Board to Cable/Wire 0.098\" (2.50mm) Solder")
      (fields (field (name "MANUFACTURER") "Phoenix Contact") (field (name "PARTNUM") "277-9964-1-ND"))
      (libsource (lib "ea_Connectors_2.5_mm_pitch") (part "1814922"))
    )
    (comp (ref "X4")
      (value "AMP188275-6")
      (footprint "AMP188275-6")
      (description "SMD Connector Female 6-Pole")
      (fields (field (name "MANUFACTURER") "AMP") (field (name "PARTNUM") "7-188275-6"))
      (libsource (lib "ea_Connectors_2.54_mm_pitch") (part "AMP188275-6"))
    )
    (comp (ref "X5")
      (value "SM03B-SRSS-TB(LF)(SN)")
      (footprint "SM03B-SRSS-TB")
      (description "CONN HEADER SH 3POS SIDE 1MM TIN")
      (fields (field (name "MANUFACTURER") "JST Sales America Inc.") (field (name "PARTNUM") "455-1803-1-ND"))
      (libsource (lib "ea_Connectors_1.0_mm_pitch") (part "SM03B-SRSS-TB(LF)(SN)"))
    )
    (comp (ref "X6")
      (value "SM03B-SRSS-TB(LF)(SN)")
      (footprint "SM03B-SRSS-TB")
      (description "CONN HEADER SH 3POS SIDE 1MM TIN")
      (fields (field (name "MANUFACTURER") "JST Sales America Inc.") (field (name "PARTNUM") "455-1803-1-ND"))
      (libsource (lib "ea_Connectors_1.0_mm_pitch") (part "SM03B-SRSS-TB(LF)(SN)"))
    )
    (comp (ref "X7")
      (value "SHF-105-01-L-D-SM")
      (footprint "SHF-105-01-L-D-SM")
      (description "10 Positions Header Connector 0.050\" (1.27mm) Surface Mount Gold")
      (fields (field (name "MANUFACTURER") "Samtec Inc.") (field (name "PARTNUM") "SAM8765-ND"))
      (libsource (lib "ea_Connectors_1.27_mm_pitch") (part "SHF-105-01-L-D-SM"))
    )
    (comp (ref "X8")
      (value "SM03B-SRSS-TB(LF)(SN)")
      (footprint "SM03B-SRSS-TB")
      (description "CONN HEADER SH 3POS SIDE 1MM TIN")
      (fields (field (name "MANUFACTURER") "JST Sales America Inc.") (field (name "PARTNUM") "455-1803-1-ND"))
      (libsource (lib "ea_Connectors_1.0_mm_pitch") (part "SM03B-SRSS-TB(LF)(SN)"))
    )
    (comp (ref "X9")
      (value "SHF-105-01-L-D-SM")
      (footprint "SHF-105-01-L-D-SM")
      (description "10 Positions Header Connector 0.050\" (1.27mm) Surface Mount Gold")
      (fields (field (name "MANUFACTURER") "Samtec Inc.") (field (name "PARTNUM") "SAM8765-ND"))
      (libsource (lib "ea_Connectors_1.27_mm_pitch") (part "SHF-105-01-L-D-SM"))
    )
  )
  (nets
    (net (code "1") (name "+3.3AV") (class "Default")
      (node (ref "C37") (pin "1") (pinfunction "1_1") (pintype "passive"))
      (node (ref "C40") (pin "2") (pinfunction "2_2") (pintype "passive"))
      (node (ref "C41") (pin "1") (pinfunction "1_1") (pintype "passive"))
      (node (ref "U11") (pin "1") (pinfunction "RESV_1") (pintype "passive"))
      (node (ref "U11") (pin "13") (pinfunction "VDD_13") (pintype "power_in"))
      (node (ref "U12") (pin "5") (pinfunction "OUT_5") (pintype "power_in"))
    )
    (net (code "2") (name "+3V3") (class "Default")
      (node (ref "C12") (pin "1") (pinfunction "1_1") (pintype "passive"))
      (node (ref "C36") (pin "2") (pinfunction "2_2") (pintype "passive"))
      (node (ref "C42") (pin "2") (pinfunction "2_2") (pintype "passive"))
      (node (ref "R14") (pin "2") (pinfunction "2_2") (pintype "passive"))
      (node (ref "R19") (pin "1") (pinfunction "1_1") (pintype "passive"))
      (node (ref "R4") (pin "2") (pinfunction "2_2") (pintype "passive"))
      (node (ref "R5") (pin "2") (pinfunction "2_2") (pintype "passive"))
      (node (ref "U1") (pin "48") (pinfunction "VREG/VREF_48") (pintype "power_in"))
      (node (ref "U11") (pin "8") (pinfunction "VDDIO_8") (pintype "power_in"))
      (node (ref "U2") (pin "3") (pinfunction "VDD_3") (pintype "power_in"))
      (node (ref "U6") (pin "5") (pinfunction "VCC_5") (pintype "power_in"))
      (node (ref "U7") (pin "5") (pinfunction "VCC_5") (pintype "power_in"))
      (node (ref "U8") (pin "5") (pinfunction "VCC_5") (pintype "power_in"))
      (node (ref "X7") (pin "1") (pinfunction "1_1") (pintype "passive"))
    )
    (net (code "3") (name "+5V") (class "Default")
      (node (ref "C13") (pin "2") (pinfunction "2_2") (pintype "passive"))
      (node (ref "C16") (pin "2") (pinfunction "2_2") (pintype "passive"))
      (node (ref "C23") (pin "2") (pinfunction "2_2") (pintype "passive"))
      (node (ref "C30") (pin "2") (pinfunction "2_2") (pintype "passive"))
      (node (ref "C31") (pin "2") (pinfunction "2_2") (pintype "passive"))
      (node (ref "C39") (pin "1") (pinfunction "1_1") (pintype "passive"))
      (node (ref "L1") (pin "2") (pinfunction "2_2") (pintype "passive"))
      (node (ref "R28") (pin "1") (pinfunction "1_1") (pintype "passive"))
      (node (ref "U12") (pin "1") (pinfunction "IN_1") (pintype "power_in"))
      (node (ref "U3") (pin "2") (pinfunction "VDD_2") (pintype "passive"))
      (node (ref "U4") (pin "2") (pinfunction "VDD_2") (pintype "passive"))
      (node (ref "U5") (pin "2") (pinfunction "VDD_2") (pintype "passive"))
      (node (ref "X4") (pin "1") (pinfunction "1_1") (pintype "passive"))
      (node (ref "X4") (pin "2") (pinfunction "2_2") (pintype "passive"))
      (node (ref "X5") (pin "1") (pinfunction "1_1") (pintype "passive"))
      (node (ref "X6") (pin "1") (pinfunction "1_1") (pintype "passive"))
      (node (ref "X7") (pin "3") (pinfunction "3_3") (pintype "passive"))
      (node (ref "X8") (pin "1") (pinfunction "1_1") (pintype "passive"))
      (node (ref "X9") (pin "10") (pinfunction "10_10") (pintype "passive"))
    )
    (net (code "4") (name "+PVDD") (class "Default")
      (node (ref "C10") (pin "2") (pinfunction "2_2") (pintype "passive"))
      (node (ref "C24") (pin "2") (pinfunction "2_2") (pintype "passive"))
      (node (ref "C29") (pin "1") (pinfunction "1_1") (pintype "passive"))
      (node (ref "C4") (pin "1") (pinfunction "1_1") (pintype "passive"))
      (node (ref "C5") (pin "1") (pinfunction "1_1") (pintype "passive"))
      (node (ref "C6") (pin "2") (pinfunction "2_2") (pintype "passive"))
      (node (ref "C7") (pin "1") (pinfunction "1_1") (pintype "passive"))
      (node (ref "C8") (pin "2") (pinfunction "2_2") (pintype "passive"))
      (node (ref "C9") (pin "1") (pinfunction "1_1") (pintype "passive"))
      (node (ref "D1") (pin "1") (pinfunction "C_1") (pintype "passive"))
      (node (ref "P4") (pin "1") (pinfunction "1_1") (pintype "passive"))
      (node (ref "Q1") (pin "5") (pinfunction "D_5") (pintype "passive"))
      (node (ref "Q1") (pin "6") (pinfunction "D_6") (pintype "passive"))
      (node (ref "Q1") (pin "7") (pinfunction "D_7") (pintype "passive"))
      (node (ref "Q1") (pin "8") (pinfunction "D_8") (pintype "passive"))
      (node (ref "Q2") (pin "5") (pinfunction "D_5") (pintype "passive"))
      (node (ref "Q2") (pin "6") (pinfunction "D_6") (pintype "passive"))
      (node (ref "Q2") (pin "7") (pinfunction "D_7") (pintype "passive"))
      (node (ref "Q2") (pin "8") (pinfunction "D_8") (pintype "passive"))
      (node (ref "Q3") (pin "5") (pinfunction "D_5") (pintype "passive"))
      (node (ref "Q3") (pin "6") (pinfunction "D_6") (pintype "passive"))
      (node (ref "Q3") (pin "7") (pinfunction "D_7") (pintype "passive"))
      (node (ref "Q3") (pin "8") (pinfunction "D_8") (pintype "passive"))
      (node (ref "R21") (pin "2") (pinfunction "2_2") (pintype "passive"))
      (node (ref "R26") (pin "2") (pinfunction "2_2") (pintype "passive"))
      (node (ref "R9") (pin "2") (pinfunction "2_2") (pintype "passive"))
      (node (ref "U1") (pin "41") (pinfunction "PVDD_41") (pintype "power_in"))
      (node (ref "U10") (pin "7") (pinfunction "VIN_7") (pintype "passive"))
      (node (ref "U9") (pin "8") (pinfunction "IN_8") (pintype "power_in"))
    )
    (net (code "5") (name "/CAN0_RX") (class "Default")
      (node (ref "U2") (pin "4") (pinfunction "RXD_4") (pintype "output"))
    )
    (net (code "6") (name "/CAN0_TX") (class "Default")
      (node (ref "U2") (pin "1") (pinfunction "TXD_1") (pintype "input"))
    )
    (net (code "7") (name "/CANCTRL") (class "Default")
      (node (ref "U2") (pin "8") (pinfunction "RS_8") (pintype "input"))
    )
    (net (code "8") (name "/CANH") (class "Default")
      (node (ref "R13") (pin "1") (pinfunction "1_1") (pintype "passive"))
      (node (ref "U2") (pin "7") (pinfunction "CANH_7") (pintype "bidirectional"))
      (node (ref "X3") (pin "1") (pinfunction "1_1") (pintype "passive"))
    )
    (net (code "9") (name "/CANL") (class "Default")
      (node (ref "R13") (pin "2") (pinfunction "2_2") (pintype "passive"))
      (node (ref "U2") (pin "6") (pinfunction "CANL_6") (pintype "bidirectional"))
      (node (ref "X3") (pin "2") (pinfunction "2_2") (pintype "passive"))
    )
    (net (code "10") (name "/ENCA") (class "Default")
      (node (ref "R29") (pin "1") (pinfunction "1_1") (pintype "passive"))
      (node (ref "R33") (pin "2") (pinfunction "2_2") (pintype "passive"))
      (node (ref "X9") (pin "4") (pinfunction "4_4") (pintype "passive"))
    )
    (net (code "11") (name "/ENCB") (class "Default")
      (node (ref "R30") (pin "1") (pinfunction "1_1") (pintype "passive"))
      (node (ref "R34") (pin "2") (pinfunction "2_2") (pintype "passive"))
      (node (ref "X9") (pin "6") (pinfunction "6_6") (pintype "passive"))
    )
    (net (code "12") (name "/ENCC") (class "Default")
      (node (ref "R31") (pin "1") (pinfunction "1_1") (pintype "passive"))
      (node (ref "R37") (pin "2") (pinfunction "2_2") (pintype "passive"))
      (node (ref "X9") (pin "8") (pinfunction "8_8") (pintype "passive"))
    )
    (net (code "13") (name "/EN_GATE") (class "Default")
      (node (ref "U1") (pin "1") (pinfunction "EN_GATE_1") (pintype "input"))
    )
    (net (code "14") (name "/EN_IMU_PWR") (class "Default")
      (node (ref "U12") (pin "3") (pinfunction "~{SHDN}_3") (pintype "power_in"))
    )
    (net (code "15") (name "/EVCC") (class "Default")
      (node (ref "C28") (pin "2") (pinfunction "2_2") (pintype "passive"))
      (node (ref "R23") (pin "2") (pinfunction "2_2") (pintype "passive"))
      (node (ref "R29") (pin "2") (pinfunction "2_2") (pintype "passive"))
      (node (ref "R30") (pin "2") (pinfunction "2_2") (pintype "passive"))
      (node (ref "R31") (pin "2") (pinfunction "2_2") (pintype "passive"))
      (node (ref "U9") (pin "1") (pinfunction "OUT_1") (pintype "power_in"))
      (node (ref "X9") (pin "2") (pinfunction "2_2") (pintype "passive"))
    )
    (net (code "16") (name "/EXT_TEMP") (class "Default")
      (node (ref "R20") (pin "1") (pinfunction "1_1") (pintype "passive"))
    )
    (net (code "17") (name "/FAULT") (class "Default")
      (node (ref "R4") (pin "1") (pinfunction "1_1") (pintype "passive"))
      (node (ref "U1") (pin "8") (pinfunction "FAULT_8") (pintype "open_collector"))
    )
    (net (code "18") (name "/FRAME_SYNC") (class "Default")
      (node (ref "U11") (pin "11") (pinfunction "FSYNC_11") (pintype "input"))
    )
    (net (code "19") (name "/FTM0_CH0") (class "Default")
      (node (ref "U3") (pin "3") (pinfunction "IN_3") (pintype "passive"))
    )
    (net (code "20") (name "/FTM0_CH1") (class "Default")
      (node (ref "U4") (pin "3") (pinfunction "IN_3") (pintype "passive"))
    )
    (net (code "21") (name "/FTM0_CH2") (class "Default")
      (node (ref "U5") (pin "3") (pinfunction "IN_3") (pintype "passive"))
    )
    (net (code "22") (name "/FTM0_CH3") (class "Default")
      (node (ref "U6") (pin "4") (pinfunction "Y_4") (pintype "open_collector"))
    )
    (net (code "23") (name "/FTM0_CH4") (class "Default")
      (node (ref "U7") (pin "4") (pinfunction "Y_4") (pintype "open_collector"))
    )
    (net (code "24") (name "/FTM0_CH5") (class "Default")
      (node (ref "U8") (pin "4") (pinfunction "Y_4") (pintype "open_collector"))
    )
    (net (code "25") (name "/FTM1_CH1") (class "Default")
      (node (ref "C33") (pin "1") (pinfunction "1_1") (pintype "passive"))
      (node (ref "R37") (pin "1") (pinfunction "1_1") (pintype "passive"))
      (node (ref "R38") (pin "1") (pinfunction "1_1") (pintype "passive"))
    )
    (net (code "26") (name "/FTM2_QD_PHA") (class "Default")
      (node (ref "C35") (pin "1") (pinfunction "1_1") (pintype "passive"))
      (node (ref "R33") (pin "1") (pinfunction "1_1") (pintype "passive"))
      (node (ref "R40") (pin "1") (pinfunction "1_1") (pintype "passive"))
    )
    (net (code "27") (name "/FTM2_QD_PHB") (class "Default")
      (node (ref "C34") (pin "1") (pinfunction "1_1") (pintype "passive"))
      (node (ref "R34") (pin "1") (pinfunction "1_1") (pintype "passive"))
      (node (ref "R39") (pin "1") (pinfunction "1_1") (pintype "passive"))
    )
    (net (code "28") (name "/GH_A") (class "Default")
      (node (ref "Q1") (pin "4") (pinfunction "G_4") (pintype "passive"))
      (node (ref "U1") (pin "36") (pinfunction "GH_A_36") (pintype "output"))
    )
    (net (code "29") (name "/GH_B") (class "Default")
      (node (ref "Q2") (pin "4") (pinfunction "G_4") (pintype "passive"))
      (node (ref "U1") (pin "29") (pinfunction "GH_B_29") (pintype "output"))
    )
    (net (code "30") (name "/GH_C") (class "Default")
      (node (ref "Q3") (pin "4") (pinfunction "G_4") (pintype "passive"))
      (node (ref "U1") (pin "28") (pinfunction "GH_C_28") (pintype "output"))
    )
    (net (code "31") (name "/GL_A") (class "Default")
      (node (ref "Q4") (pin "4") (pinfunction "G_4") (pintype "passive"))
      (node (ref "U1") (pin "33") (pinfunction "GL_A_33") (pintype "output"))
    )
    (net (code "32") (name "/GL_B") (class "Default")
      (node (ref "Q5") (pin "4") (pinfunction "G_4") (pintype "passive"))
      (node (ref "U1") (pin "32") (pinfunction "GL_B_32") (pintype "output"))
    )
    (net (code "33") (name "/GL_C") (class "Default")
      (node (ref "Q6") (pin "4") (pinfunction "G_4") (pintype "passive"))
      (node (ref "U1") (pin "25") (pinfunction "GL_C_25") (pintype "output"))
    )
    (net (code "34") (name "/I2C0_SCL") (class "Default")
      (node (ref "X7") (pin "4") (pinfunction "4_4") (pintype "passive"))
    )
    (net (code "35") (name "/I2C0_SDA") (class "Default")
      (node (ref "X7") (pin "6") (pinfunction "6_6") (pintype "passive"))
    )
    (net (code "36") (name "/I2S0_MCLK") (class "Default")
      (node (ref "X7") (pin "2") (pinfunction "2_2") (pintype "passive"))
    )
    (net (code "37") (name "/INH_A") (class "Default")
      (node (ref "U1") (pin "2") (pinfunction "INH_A_2") (pintype "input"))
    )
    (net (code "38") (name "/INH_B") (class "Default")
      (node (ref "U1") (pin "4") (pinfunction "INH_B_4") (pintype "input"))
    )
    (net (code "39") (name "/INH_C") (class "Default")
      (node (ref "U1") (pin "6") (pinfunction "INH_C_6") (pintype "input"))
    )
    (net (code "40") (name "/INL_A") (class "Default")
      (node (ref "U1") (pin "3") (pinfunction "INL_A_3") (pintype "input"))
    )
    (net (code "41") (name "/INL_B") (class "Default")
      (node (ref "U1") (pin "5") (pinfunction "INL_B_5") (pintype "input"))
    )
    (net (code "42") (name "/INL_C") (class "Default")
      (node (ref "U1") (pin "7") (pinfunction "INL_C_7") (pintype "input"))
    )
    (net (code "43") (name "/INT_9250") (class "Default")
      (node (ref "U11") (pin "12") (pinfunction "INT_12") (pintype "output"))
    )
    (net (code "44") (name "/MOT_A") (class "Default")
      (node (ref "P1") (pin "1") (pinfunction "1_1") (pintype "passive"))
      (node (ref "Q1") (pin "1") (pinfunction "S_1") (pintype "passive"))
      (node (ref "Q1") (pin "2") (pinfunction "S_2") (pintype "passive"))
      (node (ref "Q1") (pin "3") (pinfunction "S_3") (pintype "passive"))
      (node (ref "Q4") (pin "5") (pinfunction "D_5") (pintype "passive"))
      (node (ref "Q4") (pin "6") (pinfunction "D_6") (pintype "passive"))
      (node (ref "Q4") (pin "7") (pinfunction "D_7") (pintype "passive"))
      (node (ref "Q4") (pin "8") (pinfunction "D_8") (pintype "passive"))
      (node (ref "R1") (pin "2") (pinfunction "2_2") (pintype "passive"))
      (node (ref "U1") (pin "35") (pinfunction "SH_A_35") (pintype "input"))
    )
    (net (code "45") (name "/MOT_B") (class "Default")
      (node (ref "P2") (pin "1") (pinfunction "1_1") (pintype "passive"))
      (node (ref "Q2") (pin "1") (pinfunction "S_1") (pintype "passive"))
      (node (ref "Q2") (pin "2") (pinfunction "S_2") (pintype "passive"))
      (node (ref "Q2") (pin "3") (pinfunction "S_3") (pintype "passive"))
      (node (ref "Q5") (pin "5") (pinfunction "D_5") (pintype "passive"))
      (node (ref "Q5") (pin "6") (pinfunction "D_6") (pintype "passive"))
      (node (ref "Q5") (pin "7") (pinfunction "D_7") (pintype "passive"))
      (node (ref "Q5") (pin "8") (pinfunction "D_8") (pintype "passive"))
      (node (ref "R2") (pin "2") (pinfunction "2_2") (pintype "passive"))
      (node (ref "U1") (pin "30") (pinfunction "SH_B_30") (pintype "input"))
    )
    (net (code "46") (name "/MOT_C") (class "Default")
      (node (ref "P3") (pin "1") (pinfunction "1_1") (pintype "passive"))
      (node (ref "Q3") (pin "1") (pinfunction "S_1") (pintype "passive"))
      (node (ref "Q3") (pin "2") (pinfunction "S_2") (pintype "passive"))
      (node (ref "Q3") (pin "3") (pinfunction "S_3") (pintype "passive"))
      (node (ref "Q6") (pin "5") (pinfunction "D_5") (pintype "passive"))
      (node (ref "Q6") (pin "6") (pinfunction "D_6") (pintype "passive"))
      (node (ref "Q6") (pin "7") (pinfunction "D_7") (pintype "passive"))
      (node (ref "Q6") (pin "8") (pinfunction "D_8") (pintype "passive"))
      (node (ref "R3") (pin "2") (pinfunction "2_2") (pintype "passive"))
      (node (ref "U1") (pin "27") (pinfunction "SH_C_27") (pintype "input"))
    )
    (net (code "47") (name "/PWRGD") (class "Default")
      (node (ref "R5") (pin "1") (pinfunction "1_1") (pintype "passive"))
      (node (ref "U1") (pin "13") (pinfunction "PWRGD_13") (pintype "open_collector"))
    )
    (net (code "48") (name "/SL_A") (class "Default")
      (node (ref "B1") (pin "2") (pinfunction "2_2") (pintype "passive"))
      (node (ref "Q4") (pin "1") (pinfunction "S_1") (pintype "passive"))
      (node (ref "Q4") (pin "2") (pinfunction "S_2") (pintype "passive"))
      (node (ref "Q4") (pin "3") (pinfunction "S_3") (pintype "passive"))
      (node (ref "R10") (pin "2") (pinfunction "2_2") (pintype "passive"))
      (node (ref "U1") (pin "34") (pinfunction "SL_A_34") (pintype "input"))
    )
    (net (code "49") (name "/SL_B") (class "Default")
      (node (ref "B2") (pin "2") (pinfunction "2_2") (pintype "passive"))
      (node (ref "Q5") (pin "1") (pinfunction "S_1") (pintype "passive"))
      (node (ref "Q5") (pin "2") (pinfunction "S_2") (pintype "passive"))
      (node (ref "Q5") (pin "3") (pinfunction "S_3") (pintype "passive"))
      (node (ref "R11") (pin "2") (pinfunction "2_2") (pintype "passive"))
      (node (ref "U1") (pin "31") (pinfunction "SL_B_31") (pintype "input"))
    )
    (net (code "50") (name "/SL_C") (class "Default")
      (node (ref "B3") (pin "2") (pinfunction "2_2") (pintype "passive"))
      (node (ref "Q6") (pin "1") (pinfunction "S_1") (pintype "passive"))
      (node (ref "Q6") (pin "2") (pinfunction "S_2") (pintype "passive"))
      (node (ref "Q6") (pin "3") (pinfunction "S_3") (pintype "passive"))
      (node (ref "R12") (pin "2") (pinfunction "2_2") (pintype "passive"))
      (node (ref "U1") (pin "26") (pinfunction "SL_C_26") (pintype "input"))
    )
    (net (code "51") (name "/SN1") (class "Default")
      (node (ref "B1") (pin "1") (pinfunction "1_1") (pintype "passive"))
      (node (ref "C15") (pin "2") (pinfunction "2_2") (pintype "passive"))
      (node (ref "U1") (pin "23") (pinfunction "SN1_23") (pintype "input"))
    )
    (net (code "52") (name "/SN2") (class "Default")
      (node (ref "B2") (pin "1") (pinfunction "1_1") (pintype "passive"))
      (node (ref "C17") (pin "2") (pinfunction "2_2") (pintype "passive"))
      (node (ref "U1") (pin "21") (pinfunction "SN2_21") (pintype "input"))
    )
    (net (code "53") (name "/SN3") (class "Default")
      (node (ref "B3") (pin "1") (pinfunction "1_1") (pintype "passive"))
      (node (ref "C22") (pin "2") (pinfunction "2_2") (pintype "passive"))
      (node (ref "U1") (pin "19") (pinfunction "SN3_19") (pintype "input"))
    )
    (net (code "54") (name "/SNS_IA") (class "Default")
      (node (ref "C18") (pin "1") (pinfunction "1_1") (pintype "passive"))
      (node (ref "R16") (pin "1") (pinfunction "1_1") (pintype "passive"))
    )
    (net (code "55") (name "/SNS_IB") (class "Default")
      (node (ref "C19") (pin "1") (pinfunction "1_1") (pintype "passive"))
      (node (ref "R17") (pin "1") (pinfunction "1_1") (pintype "passive"))
    )
    (net (code "56") (name "/SNS_IC") (class "Default")
      (node (ref "C20") (pin "1") (pinfunction "1_1") (pintype "passive"))
      (node (ref "R18") (pin "1") (pinfunction "1_1") (pintype "passive"))
    )
    (net (code "57") (name "/SP1") (class "Default")
      (node (ref "B4") (pin "1") (pinfunction "1_1") (pintype "passive"))
      (node (ref "C15") (pin "1") (pinfunction "1_1") (pintype "passive"))
      (node (ref "U1") (pin "24") (pinfunction "SP1_24") (pintype "input"))
    )
    (net (code "58") (name "/SP2") (class "Default")
      (node (ref "B5") (pin "1") (pinfunction "1_1") (pintype "passive"))
      (node (ref "C17") (pin "1") (pinfunction "1_1") (pintype "passive"))
      (node (ref "U1") (pin "22") (pinfunction "SP2_22") (pintype "input"))
    )
    (net (code "59") (name "/SP3") (class "Default")
      (node (ref "B6") (pin "1") (pinfunction "1_1") (pintype "passive"))
      (node (ref "C22") (pin "1") (pinfunction "1_1") (pintype "passive"))
      (node (ref "U1") (pin "20") (pinfunction "SP3_20") (pintype "input"))
    )
    (net (code "60") (name "/SPI0_PCS0") (class "Default")
      (node (ref "U11") (pin "22") (pinfunction "~{CS}_22") (pintype "input"))
    )
    (net (code "61") (name "/SPI0_SCK") (class "Default")
      (node (ref "U11") (pin "23") (pinfunction "SCL/SCLK_23") (pintype "input"))
    )
    (net (code "62") (name "/SPI0_SIN") (class "Default")
      (node (ref "U11") (pin "9") (pinfunction "AD0/SDO_9") (pintype "passive"))
    )
    (net (code "63") (name "/SPI0_SOUT") (class "Default")
      (node (ref "U11") (pin "24") (pinfunction "SDA/SDI_24") (pintype "input"))
    )
    (net (code "64") (name "/SPI_CLK") (class "Default")
      (node (ref "U1") (pin "12") (pinfunction "SCLK_12") (pintype "input"))
      (node (ref "X7") (pin "9") (pinfunction "9_9") (pintype "passive"))
    )
    (net (code "65") (name "/SPI_CS0") (class "Default")
      (node (ref "X7") (pin "8") (pinfunction "8_8") (pintype "passive"))
    )
    (net (code "66") (name "/SPI_CS1") (class "Default")
      (node (ref "U1") (pin "9") (pinfunction "SCS_9") (pintype "input"))
    )
    (net (code "67") (name "/SPI_MISO") (class "Default")
      (node (ref "U1") (pin "11") (pinfunction "SDO_11") (pintype "output"))
      (node (ref "X7") (pin "7") (pinfunction "7_7") (pintype "passive"))
    )
    (net (code "68") (name "/SPI_MOSI") (class "Default")
      (node (ref "U1") (pin "10") (pinfunction "SDI_10") (pintype "input"))
      (node (ref "X7") (pin "5") (pinfunction "5_5") (pintype "passive"))
    )
    (net (code "69") (name "/TEMP") (class "Default")
      (node (ref "C14") (pin "2") (pinfunction "2_2") (pintype "passive"))
      (node (ref "R14") (pin "1") (pinfunction "1_1") (pintype "passive"))
      (node (ref "R15") (pin "2") (pinfunction "2_2") (pintype "passive"))
    )
    (net (code "70") (name "/U2SW") (class "Default")
      (node (ref "C26") (pin "1") (pinfunction "1_1") (pintype "passive"))
      (node (ref "D2") (pin "3") (pinfunction "3_3") (pintype "passive"))
      (node (ref "L1") (pin "1") (pinfunction "1_1") (pintype "passive"))
      (node (ref "U10") (pin "1") (pinfunction "SW_1") (pintype "passive"))
    )
    (net (code "71") (name "/UVDD") (class "Default")
      (node (ref "R21") (pin "1") (pinfunction "1_1") (pintype "passive"))
      (node (ref "R22") (pin "1") (pinfunction "1_1") (pintype "passive"))
    )
    (net (code "72") (name "/U_A") (class "Default")
      (node (ref "R1") (pin "1") (pinfunction "1_1") (pintype "passive"))
      (node (ref "R6") (pin "2") (pinfunction "2_2") (pintype "passive"))
    )
    (net (code "73") (name "/U_B") (class "Default")
      (node (ref "R2") (pin "1") (pinfunction "1_1") (pintype "passive"))
      (node (ref "R7") (pin "2") (pinfunction "2_2") (pintype "passive"))
    )
    (net (code "74") (name "/U_C") (class "Default")
      (node (ref "R3") (pin "1") (pinfunction "1_1") (pintype "passive"))
      (node (ref "R8") (pin "2") (pinfunction "2_2") (pintype "passive"))
    )
    (net (code "75") (name "/WAKE") (class "Default")
      (node (ref "U1") (pin "47") (pinfunction "WAKE_47") (pintype "input"))
    )
    (net (code "76") (name "GND") (class "Default")
      (node (ref "B4") (pin "2") (pinfunction "2_2") (pintype "passive"))
      (node (ref "B5") (pin "2") (pinfunction "2_2") (pintype "passive"))
      (node (ref "B6") (pin "2") (pinfunction "2_2") (pintype "passive"))
      (node (ref "B7") (pin "1") (pinfunction "1_1") (pintype "passive"))
      (node (ref "C1") (pin "1") (pinfunction "1_1") (pintype "passive"))
      (node (ref "C10") (pin "1") (pinfunction "1_1") (pintype "passive"))
      (node (ref "C12") (pin "2") (pinfunction "2_2") (pintype "passive"))
      (node (ref "C13") (pin "1") (pinfunction "1_1") (pintype "passive"))
      (node (ref "C16") (pin "1") (pinfunction "1_1") (pintype "passive"))
      (node (ref "C18") (pin "2") (pinfunction "2_2") (pintype "passive"))
      (node (ref "C19") (pin "2") (pinfunction "2_2") (pintype "passive"))
      (node (ref "C2") (pin "1") (pinfunction "1_1") (pintype "passive"))
      (node (ref "C20") (pin "2") (pinfunction "2_2") (pintype "passive"))
      (node (ref "C21") (pin "1") (pinfunction "1_1") (pintype "passive"))
      (node (ref "C23") (pin "1") (pinfunction "1_1") (pintype "passive"))
      (node (ref "C25") (pin "1") (pinfunction "1_1") (pintype "passive"))
      (node (ref "C28") (pin "1") (pinfunction "1_1") (pintype "passive"))
      (node (ref "C29") (pin "2") (pinfunction "2_2") (pintype "passive"))
      (node (ref "C30") (pin "1") (pinfunction "1_1") (pintype "passive"))
      (node (ref "C31") (pin "1") (pinfunction "1_1") (pintype "passive"))
      (node (ref "C32") (pin "2") (pinfunction "2_2") (pintype "passive"))
      (node (ref "C33") (pin "2") (pinfunction "2_2") (pintype "passive"))
      (node (ref "C34") (pin "2") (pinfunction "2_2") (pintype "passive"))
      (node (ref "C35") (pin "2") (pinfunction "2_2") (pintype "passive"))
      (node (ref "C36") (pin "1") (pinfunction "1_1") (pintype "passive"))
      (node (ref "C37") (pin "2") (pinfunction "2_2") (pintype "passive"))
      (node (ref "C38") (pin "1") (pinfunction "1_1") (pintype "passive"))
      (node (ref "C39") (pin "2") (pinfunction "2_2") (pintype "passive"))
      (node (ref "C4") (pin "2") (pinfunction "2_2") (pintype "passive"))
      (node (ref "C41") (pin "2") (pinfunction "2_2") (pintype "passive"))
      (node (ref "C42") (pin "1") (pinfunction "1_1") (pintype "passive"))
      (node (ref "C5") (pin "2") (pinfunction "2_2") (pintype "passive"))
      (node (ref "C6") (pin "1") (pinfunction "1_1") (pintype "passive"))
      (node (ref "C7") (pin "2") (pinfunction "2_2") (pintype "passive"))
      (node (ref "C8") (pin "1") (pinfunction "1_1") (pintype "passive"))
      (node (ref "C9") (pin "2") (pinfunction "2_2") (pintype "passive"))
      (node (ref "D1") (pin "2") (pinfunction "A_2") (pintype "passive"))
      (node (ref "D2") (pin "1") (pinfunction "1_1") (pintype "passive"))
      (node (ref "D2") (pin "2") (pinfunction "2_2") (pintype "passive"))
      (node (ref "P5") (pin "1") (pinfunction "1_1") (pintype "passive"))
      (node (ref "R10") (pin "1") (pinfunction "1_1") (pintype "passive"))
      (node (ref "R11") (pin "1") (pinfunction "1_1") (pintype "passive"))
      (node (ref "R12") (pin "1") (pinfunction "1_1") (pintype "passive"))
      (node (ref "R22") (pin "2") (pinfunction "2_2") (pintype "passive"))
      (node (ref "R24") (pin "1") (pinfunction "1_1") (pintype "passive"))
      (node (ref "R25") (pin "2") (pinfunction "2_2") (pintype "passive"))
      (node (ref "R32") (pin "1") (pinfunction "1_1") (pintype "passive"))
      (node (ref "R35") (pin "1") (pinfunction "1_1") (pintype "passive"))
      (node (ref "R36") (pin "1") (pinfunction "1_1") (pintype "passive"))
      (node (ref "R38") (pin "2") (pinfunction "2_2") (pintype "passive"))
      (node (ref "R39") (pin "2") (pinfunction "2_2") (pintype "passive"))
      (node (ref "R40") (pin "2") (pinfunction "2_2") (pintype "passive"))
      (node (ref "R6") (pin "1") (pinfunction "1_1") (pintype "passive"))
      (node (ref "R7") (pin "1") (pinfunction "1_1") (pintype "passive"))
      (node (ref "R8") (pin "1") (pinfunction "1_1") (pintype "passive"))
      (node (ref "U1") (pin "14") (pinfunction "GND_14") (pintype "power_in"))
      (node (ref "U1") (pin "45") (pinfunction "GND_45") (pintype "power_in"))
      (node (ref "U1") (pin "49") (pinfunction "PAD_49") (pintype "power_in"))
      (node (ref "U10") (pin "5") (pinfunction "GND_5") (pintype "passive"))
      (node (ref "U10") (pin "9") (pinfunction "GND_9") (pintype "passive"))
      (node (ref "U11") (pin "18") (pinfunction "GND_18") (pintype "passive"))
      (node (ref "U11") (pin "20") (pinfunction "RESV_20") (pintype "passive"))
      (node (ref "U12") (pin "2") (pinfunction "GND_2") (pintype "power_in"))
      (node (ref "U2") (pin "2") (pinfunction "GND_2") (pintype "power_in"))
      (node (ref "U3") (pin "4") (pinfunction "GND_4") (pintype "passive"))
      (node (ref "U4") (pin "4") (pinfunction "GND_4") (pintype "passive"))
      (node (ref "U5") (pin "4") (pinfunction "GND_4") (pintype "passive"))
      (node (ref "U6") (pin "3") (pinfunction "GND_3") (pintype "power_in"))
      (node (ref "U7") (pin "3") (pinfunction "GND_3") (pintype "power_in"))
      (node (ref "U8") (pin "3") (pinfunction "GND_3") (pintype "power_in"))
      (node (ref "U9") (pin "2") (pinfunction "GND_2") (pintype "power_in"))
      (node (ref "U9") (pin "3") (pinfunction "GND_3") (pintype "power_in"))
      (node (ref "U9") (pin "6") (pinfunction "GND_6") (pintype "power_in"))
      (node (ref "U9") (pin "7") (pinfunction "GND_7") (pintype "power_in"))
      (node (ref "X3") (pin "3") (pinfunction "3_3") (pintype "passive"))
      (node (ref "X4") (pin "5") (pinfunction "5_5") (pintype "passive"))
      (node (ref "X4") (pin "6") (pinfunction "6_6") (pintype "passive"))
      (node (ref "X5") (pin "3") (pinfunction "3_3") (pintype "passive"))
      (node (ref "X6") (pin "3") (pinfunction "3_3") (pintype "passive"))
      (node (ref "X7") (pin "10") (pinfunction "10_10") (pintype "passive"))
      (node (ref "X8") (pin "3") (pinfunction "3_3") (pintype "passive"))
      (node (ref "X9") (pin "1") (pinfunction "1_1") (pintype "passive"))
      (node (ref "X9") (pin "3") (pinfunction "3_3") (pintype "passive"))
      (node (ref "X9") (pin "5") (pinfunction "5_5") (pintype "passive"))
      (node (ref "X9") (pin "7") (pinfunction "7_7") (pintype "passive"))
      (node (ref "X9") (pin "9") (pinfunction "9_9") (pintype "passive"))
    )
    (net (code "77") (name "Net-(B7-Pad2)") (class "Default")
      (node (ref "B7") (pin "2") (pinfunction "2_2") (pintype "passive"))
      (node (ref "C14") (pin "1") (pinfunction "1_1") (pintype "passive"))
      (node (ref "R15") (pin "1") (pinfunction "1_1") (pintype "passive"))
    )
    (net (code "78") (name "Net-(C32-Pad1)") (class "Default")
      (node (ref "C32") (pin "1") (pinfunction "1_1") (pintype "passive"))
      (node (ref "R27") (pin "2") (pinfunction "2_2") (pintype "passive"))
    )
    (net (code "79") (name "Net-(U1-AVDD)") (class "Default")
      (node (ref "C2") (pin "2") (pinfunction "2_2") (pintype "passive"))
      (node (ref "U1") (pin "15") (pinfunction "AVDD_15") (pintype "power_in"))
    )
    (net (code "80") (name "Net-(U1-CP1H)") (class "Default")
      (node (ref "C3") (pin "1") (pinfunction "1_1") (pintype "passive"))
      (node (ref "U1") (pin "43") (pinfunction "CP1H_43") (pintype "passive"))
    )
    (net (code "81") (name "Net-(U1-CP1L)") (class "Default")
      (node (ref "C3") (pin "2") (pinfunction "2_2") (pintype "passive"))
      (node (ref "U1") (pin "42") (pinfunction "CP1L_42") (pintype "passive"))
    )
    (net (code "82") (name "Net-(U1-CP2H)") (class "Default")
      (node (ref "C11") (pin "1") (pinfunction "1_1") (pintype "passive"))
      (node (ref "U1") (pin "39") (pinfunction "CP2H_39") (pintype "passive"))
    )
    (net (code "83") (name "Net-(U1-CP2L)") (class "Default")
      (node (ref "C11") (pin "2") (pinfunction "2_2") (pintype "passive"))
      (node (ref "U1") (pin "40") (pinfunction "CP2L_40") (pintype "passive"))
    )
    (net (code "84") (name "Net-(U1-DVDD)") (class "Default")
      (node (ref "C1") (pin "2") (pinfunction "2_2") (pintype "passive"))
      (node (ref "U1") (pin "46") (pinfunction "DVDD_46") (pintype "power_in"))
    )
    (net (code "85") (name "Net-(U1-SO1)") (class "Default")
      (node (ref "R16") (pin "2") (pinfunction "2_2") (pintype "passive"))
      (node (ref "U1") (pin "16") (pinfunction "SO1_16") (pintype "output"))
    )
    (net (code "86") (name "Net-(U1-SO2)") (class "Default")
      (node (ref "R17") (pin "2") (pinfunction "2_2") (pintype "passive"))
      (node (ref "U1") (pin "17") (pinfunction "SO2_17") (pintype "output"))
    )
    (net (code "87") (name "Net-(U1-SO3)") (class "Default")
      (node (ref "R18") (pin "2") (pinfunction "2_2") (pintype "passive"))
      (node (ref "U1") (pin "18") (pinfunction "SO3_18") (pintype "output"))
    )
    (net (code "88") (name "Net-(U1-VCPH)") (class "Default")
      (node (ref "C24") (pin "1") (pinfunction "1_1") (pintype "passive"))
      (node (ref "U1") (pin "38") (pinfunction "VCPH_38") (pintype "passive"))
    )
    (net (code "89") (name "Net-(U1-VCP_LSD)") (class "Default")
      (node (ref "C21") (pin "2") (pinfunction "2_2") (pintype "passive"))
      (node (ref "U1") (pin "37") (pinfunction "VCP_LSD_37") (pintype "passive"))
    )
    (net (code "90") (name "Net-(U1-VDRAIN)") (class "Default")
      (node (ref "R9") (pin "1") (pinfunction "1_1") (pintype "passive"))
      (node (ref "U1") (pin "44") (pinfunction "VDRAIN_44") (pintype "power_in"))
    )
    (net (code "91") (name "Net-(U3-OUT)") (class "Default")
      (node (ref "U3") (pin "5") (pinfunction "OUT_5") (pintype "passive"))
      (node (ref "X4") (pin "4") (pinfunction "4_4") (pintype "passive"))
    )
    (net (code "92") (name "Net-(U4-OUT)") (class "Default")
      (node (ref "U4") (pin "5") (pinfunction "OUT_5") (pintype "passive"))
      (node (ref "U6") (pin "2") (pinfunction "A_2") (pintype "input"))
      (node (ref "X5") (pin "2") (pinfunction "2_2") (pintype "passive"))
    )
    (net (code "93") (name "Net-(U5-OUT)") (class "Default")
      (node (ref "U5") (pin "5") (pinfunction "OUT_5") (pintype "passive"))
      (node (ref "U7") (pin "2") (pinfunction "A_2") (pintype "input"))
      (node (ref "X6") (pin "2") (pinfunction "2_2") (pintype "passive"))
    )
    (net (code "94") (name "Net-(U8-A)") (class "Default")
      (node (ref "C25") (pin "2") (pinfunction "2_2") (pintype "passive"))
      (node (ref "R19") (pin "2") (pinfunction "2_2") (pintype "passive"))
      (node (ref "R20") (pin "2") (pinfunction "2_2") (pintype "passive"))
      (node (ref "U8") (pin "2") (pinfunction "A_2") (pintype "input"))
      (node (ref "X8") (pin "2") (pinfunction "2_2") (pintype "passive"))
    )
    (net (code "95") (name "Net-(U9-ADJ)") (class "Default")
      (node (ref "R23") (pin "1") (pinfunction "1_1") (pintype "passive"))
      (node (ref "R24") (pin "2") (pinfunction "2_2") (pintype "passive"))
      (node (ref "U9") (pin "4") (pinfunction "ADJ_4") (pintype "power_in"))
    )
    (net (code "96") (name "Net-(U9-OFF)") (class "Default")
      (node (ref "R25") (pin "1") (pinfunction "1_1") (pintype "passive"))
      (node (ref "U9") (pin "5") (pinfunction "OFF_5") (pintype "power_in"))
    )
    (net (code "97") (name "Net-(U10-BOOT)") (class "Default")
      (node (ref "C26") (pin "2") (pinfunction "2_2") (pintype "passive"))
      (node (ref "U10") (pin "8") (pinfunction "BOOT_8") (pintype "passive"))
    )
    (net (code "98") (name "Net-(U10-COMP)") (class "Default")
      (node (ref "R27") (pin "1") (pinfunction "1_1") (pintype "passive"))
      (node (ref "U10") (pin "3") (pinfunction "COMP_3") (pintype "passive"))
    )
    (net (code "99") (name "Net-(U10-EN)") (class "Default")
      (node (ref "R26") (pin "1") (pinfunction "1_1") (pintype "passive"))
      (node (ref "R35") (pin "2") (pinfunction "2_2") (pintype "passive"))
      (node (ref "U10") (pin "2") (pinfunction "EN_2") (pintype "passive"))
    )
    (net (code "100") (name "Net-(U10-FB)") (class "Default")
      (node (ref "R28") (pin "2") (pinfunction "2_2") (pintype "passive"))
      (node (ref "R36") (pin "2") (pinfunction "2_2") (pintype "passive"))
      (node (ref "U10") (pin "4") (pinfunction "FB_4") (pintype "passive"))
    )
    (net (code "101") (name "Net-(U10-FREQ)") (class "Default")
      (node (ref "R32") (pin "2") (pinfunction "2_2") (pintype "passive"))
      (node (ref "U10") (pin "6") (pinfunction "FREQ_6") (pintype "passive"))
    )
    (net (code "102") (name "Net-(U11-REGOUT)") (class "Default")
      (node (ref "C38") (pin "2") (pinfunction "2_2") (pintype "passive"))
      (node (ref "U11") (pin "10") (pinfunction "REGOUT_10") (pintype "passive"))
    )
    (net (code "103") (name "Net-(U12-BYP)") (class "Default")
      (node (ref "C40") (pin "1") (pinfunction "1_1") (pintype "passive"))
      (node (ref "U12") (pin "4") (pinfunction "BYP_4") (pintype "power_in"))
    )
    (net (code "104") (name "unconnected-(U2-VREF-Pad5)") (class "Default")
      (node (ref "U2") (pin "5") (pinfunction "VREF_5") (pintype "passive"))
    )
    (net (code "105") (name "unconnected-(U11-AUX_CL-Pad7)") (class "Default")
      (node (ref "U11") (pin "7") (pinfunction "AUX_CL_7") (pintype "bidirectional"))
    )
    (net (code "106") (name "unconnected-(U11-AUX_DA-Pad21)") (class "Default")
      (node (ref "U11") (pin "21") (pinfunction "AUX_DA_21") (pintype "bidirectional"))
    )
    (net (code "107") (name "unconnected-(U11-NC-Pad2)") (class "Default")
      (node (ref "U11") (pin "2") (pinfunction "NC_2") (pintype "passive"))
    )
    (net (code "108") (name "unconnected-(U11-NC-Pad3)") (class "Default")
      (node (ref "U11") (pin "3") (pinfunction "NC_3") (pintype "passive"))
    )
    (net (code "109") (name "unconnected-(U11-NC-Pad4)") (class "Default")
      (node (ref "U11") (pin "4") (pinfunction "NC_4") (pintype "passive"))
    )
    (net (code "110") (name "unconnected-(U11-NC-Pad5)") (class "Default")
      (node (ref "U11") (pin "5") (pinfunction "NC_5") (pintype "passive"))
    )
    (net (code "111") (name "unconnected-(U11-NC-Pad6)") (class "Default")
      (node (ref "U11") (pin "6") (pinfunction "NC_6") (pintype "passive"))
    )
    (net (code "112") (name "unconnected-(U11-NC-Pad14)") (class "Default")
      (node (ref "U11") (pin "14") (pinfunction "NC_14") (pintype "passive"))
    )
    (net (code "113") (name "unconnected-(U11-NC-Pad15)") (class "Default")
      (node (ref "U11") (pin "15") (pinfunction "NC_15") (pintype "passive"))
    )
    (net (code "114") (name "unconnected-(U11-NC-Pad16)") (class "Default")
      (node (ref "U11") (pin "16") (pinfunction "NC_16") (pintype "passive"))
    )
    (net (code "115") (name "unconnected-(U11-NC-Pad17)") (class "Default")
      (node (ref "U11") (pin "17") (pinfunction "NC_17") (pintype "passive"))
    )
    (net (code "116") (name "unconnected-(U11-RESV-Pad19)") (class "Default")
      (node (ref "U11") (pin "19") (pinfunction "RESV_19") (pintype "passive"))
    )
    (net (code "117") (name "unconnected-(X4-Pad3)") (class "Default")
      (node (ref "X4") (pin "3") (pinfunction "3_3") (pintype "passive"))
    )
  )
)
